# untitled.net
KiCad netlist of a schematic drawn in EAGLE
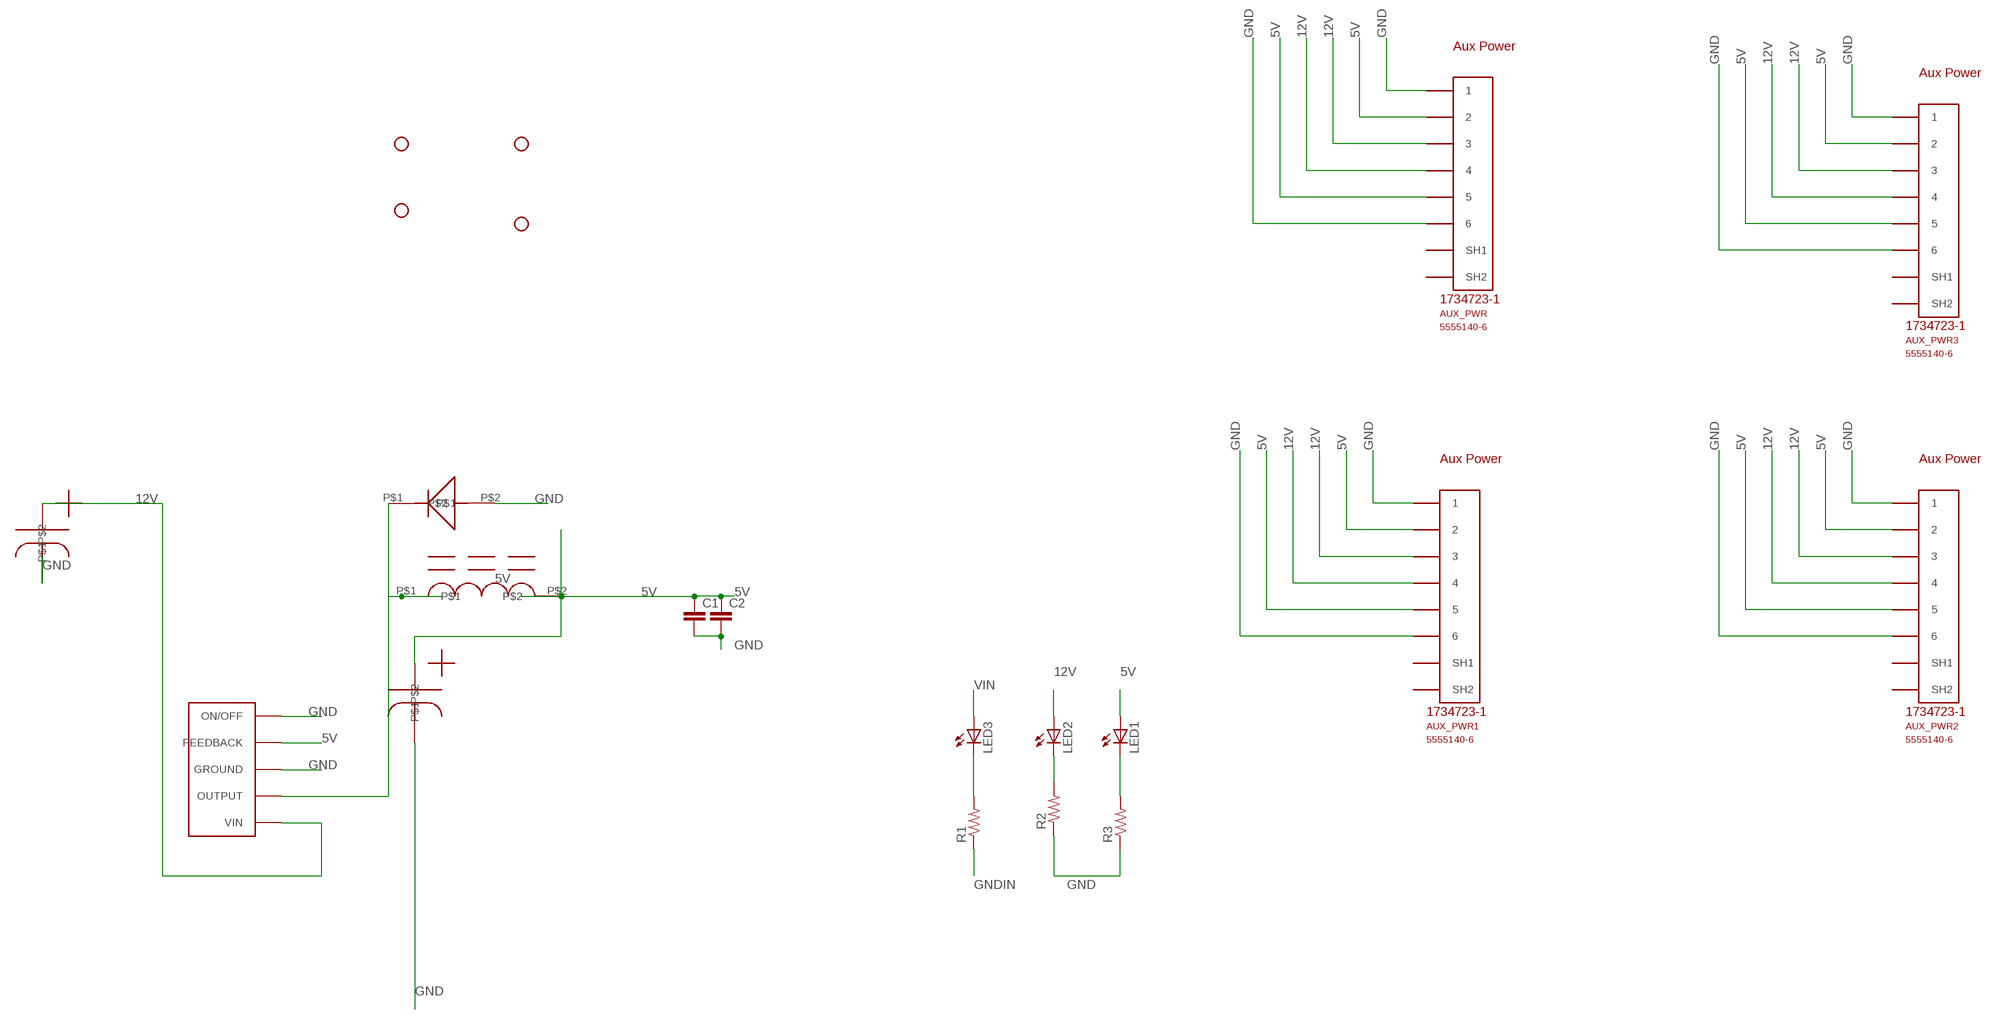
[diagram p0: schematic, sheet 1]
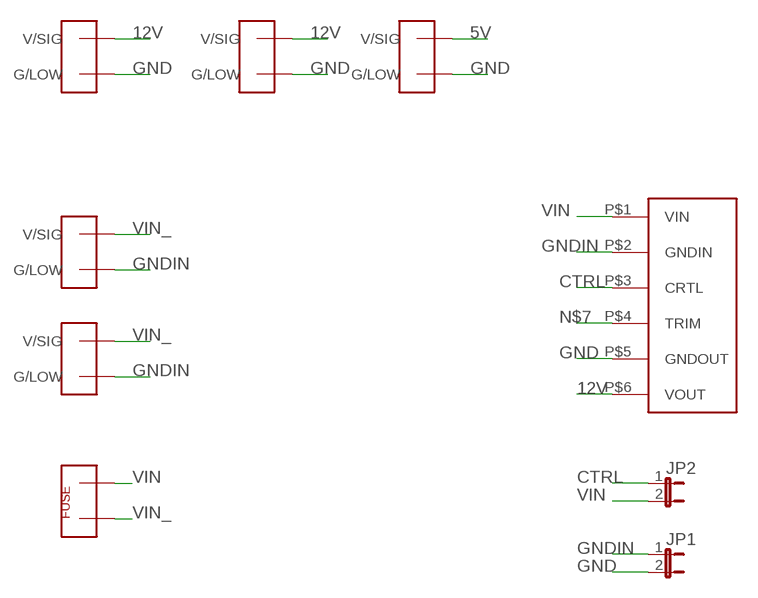
[diagram p1: schematic, sheet 2]

(export (version "E")
  (design (tool "Eeschema 10.0.6"))
  (components
    (comp (ref "AUX_PWR")
      (value "5555140-6")
      (footprint "eagle-import:1734723-1_RJ11")
      (libsource (lib "eagle-import") (part "5555140-6"))
    )
    (comp (ref "AUX_PWR1")
      (value "5555140-6")
      (footprint "eagle-import:1734723-1_RJ11")
      (libsource (lib "eagle-import") (part "5555140-6"))
    )
    (comp (ref "AUX_PWR2")
      (value "5555140-6")
      (footprint "eagle-import:1734723-1_RJ11")
      (libsource (lib "eagle-import") (part "5555140-6"))
    )
    (comp (ref "AUX_PWR3")
      (value "5555140-6")
      (footprint "eagle-import:1734723-1_RJ11")
      (libsource (lib "eagle-import") (part "5555140-6"))
    )
    (comp (ref "C1")
      (value "CAP0805")
      (footprint "eagle-import:0805")
      (libsource (lib "eagle-import") (part "CAP0805"))
    )
    (comp (ref "C2")
      (value "CAP0805")
      (footprint "eagle-import:0805")
      (libsource (lib "eagle-import") (part "CAP0805"))
    )
    (comp (ref "H1")
      (value "STAND-OFF")
      (footprint "eagle-import:STAND-OFF")
      (libsource (lib "eagle-import") (part "STAND-OFF"))
    )
    (comp (ref "H2")
      (value "STAND-OFF")
      (footprint "eagle-import:STAND-OFF")
      (libsource (lib "eagle-import") (part "STAND-OFF"))
    )
    (comp (ref "H3")
      (value "STAND-OFF")
      (footprint "eagle-import:STAND-OFF")
      (libsource (lib "eagle-import") (part "STAND-OFF"))
    )
    (comp (ref "H4")
      (value "STAND-OFF")
      (footprint "eagle-import:STAND-OFF")
      (libsource (lib "eagle-import") (part "STAND-OFF"))
    )
    (comp (ref "LED1")
      (value "LEDCHIP-LED0805")
      (footprint "eagle-import:CHIP-LED0805")
      (libsource (lib "eagle-import") (part "LEDCHIP-LED0805"))
    )
    (comp (ref "LED2")
      (value "LEDCHIP-LED0805")
      (footprint "eagle-import:CHIP-LED0805")
      (libsource (lib "eagle-import") (part "LEDCHIP-LED0805"))
    )
    (comp (ref "LED3")
      (value "LEDCHIP-LED0805")
      (footprint "eagle-import:CHIP-LED0805")
      (libsource (lib "eagle-import") (part "LEDCHIP-LED0805"))
    )
    (comp (ref "R1")
      (value "R-US_M0805")
      (footprint "eagle-import:M0805")
      (libsource (lib "eagle-import") (part "R-US_M0805"))
    )
    (comp (ref "R2")
      (value "R-US_M0805")
      (footprint "eagle-import:M0805")
      (libsource (lib "eagle-import") (part "R-US_M0805"))
    )
    (comp (ref "R3")
      (value "R-US_M0805")
      (footprint "eagle-import:M0805")
      (libsource (lib "eagle-import") (part "R-US_M0805"))
    )
    (comp (ref "U$4")
      (value "MBR360GOS")
      (footprint "eagle-import:MBR360GOS")
      (libsource (lib "eagle-import") (part "MBR360GOS"))
    )
    (comp (ref "U$7")
      (value "LM2576")
      (footprint "eagle-import:D2PAK-5")
      (libsource (lib "eagle-import") (part "LM2576"))
    )
    (comp (ref "U$8")
      (value "CAPESK107M025AC3AA")
      (footprint "eagle-import:ESK107M025AC3AA")
      (libsource (lib "eagle-import") (part "CAPESK107M025AC3AA"))
    )
    (comp (ref "U$9")
      (value "CAPESK108M025AH4EA")
      (footprint "eagle-import:ESK108M025AH4EA")
      (libsource (lib "eagle-import") (part "CAPESK108M025AH4EA"))
    )
    (comp (ref "U$10")
      (value "M1418-ND")
      (footprint "eagle-import:M1418-ND")
      (libsource (lib "eagle-import") (part "M1418-ND"))
    )
    (comp (ref "JP1")
      (value "JP1E")
      (footprint "eagle-import:JP1")
      (libsource (lib "eagle-import") (part "JP1E"))
    )
    (comp (ref "JP2")
      (value "JP1E")
      (footprint "eagle-import:JP1")
      (libsource (lib "eagle-import") (part "JP1E"))
    )
    (comp (ref "U$1")
      (value "TE770966")
      (footprint "eagle-import:2X1-MATE-N-LOCK")
      (libsource (lib "eagle-import") (part "TE770966"))
    )
    (comp (ref "U$2")
      (value "TE770966")
      (footprint "eagle-import:2X1-MATE-N-LOCK")
      (libsource (lib "eagle-import") (part "TE770966"))
    )
    (comp (ref "U$3")
      (value "TE770966")
      (footprint "eagle-import:2X1-MATE-N-LOCK")
      (libsource (lib "eagle-import") (part "TE770966"))
    )
    (comp (ref "U$12")
      (value "RPA60-2412SFW_P")
      (footprint "eagle-import:RPA60-2412SFW_P")
      (libsource (lib "eagle-import") (part "RPA60-2412SFW_P"))
    )
    (comp (ref "U$13")
      (value "FUSEMINI-BLADE")
      (footprint "eagle-import:MINI-BLADE-FUSE")
      (libsource (lib "eagle-import") (part "FUSEMINI-BLADE"))
    )
    (comp (ref "U$14")
      (value "TE770966")
      (footprint "eagle-import:2X1-MATE-N-LOCK")
      (libsource (lib "eagle-import") (part "TE770966"))
    )
    (comp (ref "U$15")
      (value "TE770966")
      (footprint "eagle-import:2X1-MATE-N-LOCK")
      (libsource (lib "eagle-import") (part "TE770966"))
    )
  )
  (nets
    (net (code "1") (name "5V") (class "Default")
      (node (ref "AUX_PWR") (pin "2") (pinfunction "2_2") (pintype "bidirectional"))
      (node (ref "AUX_PWR") (pin "5") (pinfunction "5_5") (pintype "bidirectional"))
      (node (ref "AUX_PWR1") (pin "2") (pinfunction "2_2") (pintype "bidirectional"))
      (node (ref "AUX_PWR1") (pin "5") (pinfunction "5_5") (pintype "bidirectional"))
      (node (ref "AUX_PWR2") (pin "2") (pinfunction "2_2") (pintype "bidirectional"))
      (node (ref "AUX_PWR2") (pin "5") (pinfunction "5_5") (pintype "bidirectional"))
      (node (ref "AUX_PWR3") (pin "2") (pinfunction "2_2") (pintype "bidirectional"))
      (node (ref "AUX_PWR3") (pin "5") (pinfunction "5_5") (pintype "bidirectional"))
      (node (ref "C1") (pin "1") (pinfunction "1_1") (pintype "passive"))
      (node (ref "C2") (pin "1") (pinfunction "1_1") (pintype "passive"))
      (node (ref "LED1") (pin "A") (pinfunction "A_A") (pintype "passive"))
      (node (ref "U$10") (pin "P$2") (pinfunction "P$2_P$2") (pintype "bidirectional"))
      (node (ref "U$3") (pin "CIRCUIT1") (pinfunction "V/SIG_CIRCUIT1") (pintype "bidirectional"))
      (node (ref "U$7") (pin "4") (pinfunction "FEEDBACK_4") (pintype "bidirectional"))
      (node (ref "U$9") (pin "P$1") (pinfunction "P$1_P$1") (pintype "bidirectional"))
    )
    (net (code "2") (name "12V") (class "Default")
      (node (ref "AUX_PWR") (pin "3") (pinfunction "3_3") (pintype "bidirectional"))
      (node (ref "AUX_PWR") (pin "4") (pinfunction "4_4") (pintype "bidirectional"))
      (node (ref "AUX_PWR1") (pin "3") (pinfunction "3_3") (pintype "bidirectional"))
      (node (ref "AUX_PWR1") (pin "4") (pinfunction "4_4") (pintype "bidirectional"))
      (node (ref "AUX_PWR2") (pin "3") (pinfunction "3_3") (pintype "bidirectional"))
      (node (ref "AUX_PWR2") (pin "4") (pinfunction "4_4") (pintype "bidirectional"))
      (node (ref "AUX_PWR3") (pin "3") (pinfunction "3_3") (pintype "bidirectional"))
      (node (ref "AUX_PWR3") (pin "4") (pinfunction "4_4") (pintype "bidirectional"))
      (node (ref "LED2") (pin "A") (pinfunction "A_A") (pintype "passive"))
      (node (ref "U$1") (pin "CIRCUIT1") (pinfunction "V/SIG_CIRCUIT1") (pintype "bidirectional"))
      (node (ref "U$12") (pin "P$6") (pinfunction "VOUT_P$6") (pintype "bidirectional"))
      (node (ref "U$2") (pin "CIRCUIT1") (pinfunction "V/SIG_CIRCUIT1") (pintype "bidirectional"))
      (node (ref "U$7") (pin "1") (pinfunction "VIN_1") (pintype "bidirectional"))
      (node (ref "U$8") (pin "P$1") (pinfunction "P$1_P$1") (pintype "bidirectional"))
    )
    (net (code "3") (name "CTRL") (class "Default")
      (node (ref "JP2") (pin "1") (pinfunction "1_1") (pintype "passive"))
      (node (ref "U$12") (pin "P$3") (pinfunction "CRTL_P$3") (pintype "bidirectional"))
    )
    (net (code "4") (name "GND") (class "Default")
      (node (ref "AUX_PWR") (pin "1") (pinfunction "1_1") (pintype "bidirectional"))
      (node (ref "AUX_PWR") (pin "6") (pinfunction "6_6") (pintype "bidirectional"))
      (node (ref "AUX_PWR1") (pin "1") (pinfunction "1_1") (pintype "bidirectional"))
      (node (ref "AUX_PWR1") (pin "6") (pinfunction "6_6") (pintype "bidirectional"))
      (node (ref "AUX_PWR2") (pin "1") (pinfunction "1_1") (pintype "bidirectional"))
      (node (ref "AUX_PWR2") (pin "6") (pinfunction "6_6") (pintype "bidirectional"))
      (node (ref "AUX_PWR3") (pin "1") (pinfunction "1_1") (pintype "bidirectional"))
      (node (ref "AUX_PWR3") (pin "6") (pinfunction "6_6") (pintype "bidirectional"))
      (node (ref "C1") (pin "2") (pinfunction "2_2") (pintype "passive"))
      (node (ref "C2") (pin "2") (pinfunction "2_2") (pintype "passive"))
      (node (ref "JP1") (pin "2") (pinfunction "2_2") (pintype "passive"))
      (node (ref "R2") (pin "1") (pinfunction "1_1") (pintype "passive"))
      (node (ref "R3") (pin "1") (pinfunction "1_1") (pintype "passive"))
      (node (ref "U$1") (pin "CIRCUIT2") (pinfunction "G/LOW_CIRCUIT2") (pintype "bidirectional"))
      (node (ref "U$12") (pin "P$5") (pinfunction "GNDOUT_P$5") (pintype "bidirectional"))
      (node (ref "U$2") (pin "CIRCUIT2") (pinfunction "G/LOW_CIRCUIT2") (pintype "bidirectional"))
      (node (ref "U$3") (pin "CIRCUIT2") (pinfunction "G/LOW_CIRCUIT2") (pintype "bidirectional"))
      (node (ref "U$4") (pin "P$2") (pinfunction "P$1_P$2") (pintype "bidirectional"))
      (node (ref "U$7") (pin "3") (pinfunction "GROUND_3") (pintype "bidirectional"))
      (node (ref "U$7") (pin "5") (pinfunction "ON/OFF_5") (pintype "bidirectional"))
      (node (ref "U$7") (pin "GROUND") (pinfunction "GROUND_GROUND") (pintype "bidirectional"))
      (node (ref "U$8") (pin "P$2") (pinfunction "P$2_P$2") (pintype "bidirectional"))
      (node (ref "U$9") (pin "P$2") (pinfunction "P$2_P$2") (pintype "bidirectional"))
    )
    (net (code "5") (name "GNDIN") (class "Default")
      (node (ref "JP1") (pin "1") (pinfunction "1_1") (pintype "passive"))
      (node (ref "R1") (pin "1") (pinfunction "1_1") (pintype "passive"))
      (node (ref "U$12") (pin "P$2") (pinfunction "GNDIN_P$2") (pintype "bidirectional"))
      (node (ref "U$14") (pin "CIRCUIT2") (pinfunction "G/LOW_CIRCUIT2") (pintype "bidirectional"))
      (node (ref "U$15") (pin "CIRCUIT2") (pinfunction "G/LOW_CIRCUIT2") (pintype "bidirectional"))
    )
    (net (code "6") (name "N$7") (class "Default")
      (node (ref "U$12") (pin "P$4") (pinfunction "TRIM_P$4") (pintype "bidirectional"))
    )
    (net (code "7") (name "Net-(LED1-PadC)") (class "Default")
      (node (ref "LED1") (pin "C") (pinfunction "C_C") (pintype "passive"))
      (node (ref "R3") (pin "2") (pinfunction "2_2") (pintype "passive"))
    )
    (net (code "8") (name "Net-(LED2-PadC)") (class "Default")
      (node (ref "LED2") (pin "C") (pinfunction "C_C") (pintype "passive"))
      (node (ref "R2") (pin "2") (pinfunction "2_2") (pintype "passive"))
    )
    (net (code "9") (name "Net-(LED3-PadC)") (class "Default")
      (node (ref "LED3") (pin "C") (pinfunction "C_C") (pintype "passive"))
      (node (ref "R1") (pin "2") (pinfunction "2_2") (pintype "passive"))
    )
    (net (code "10") (name "Net-(U$4-P$2)") (class "Default")
      (node (ref "U$10") (pin "P$1") (pinfunction "P$1_P$1") (pintype "bidirectional"))
      (node (ref "U$4") (pin "P$1") (pinfunction "P$2_P$1") (pintype "bidirectional"))
      (node (ref "U$7") (pin "2") (pinfunction "OUTPUT_2") (pintype "bidirectional"))
    )
    (net (code "11") (name "VIN") (class "Default")
      (node (ref "JP2") (pin "2") (pinfunction "2_2") (pintype "passive"))
      (node (ref "LED3") (pin "A") (pinfunction "A_A") (pintype "passive"))
      (node (ref "U$12") (pin "P$1") (pinfunction "VIN_P$1") (pintype "bidirectional"))
      (node (ref "U$13") (pin "OUT") (pinfunction "OUT_OUT") (pintype "bidirectional"))
    )
    (net (code "12") (name "VIN_") (class "Default")
      (node (ref "U$13") (pin "IN") (pinfunction "IN_IN") (pintype "bidirectional"))
      (node (ref "U$14") (pin "CIRCUIT1") (pinfunction "V/SIG_CIRCUIT1") (pintype "bidirectional"))
      (node (ref "U$15") (pin "CIRCUIT1") (pinfunction "V/SIG_CIRCUIT1") (pintype "bidirectional"))
    )
    (net (code "13") (name "unconnected-(AUX_PWR-PadSH1)") (class "Default")
      (node (ref "AUX_PWR") (pin "SH1") (pinfunction "SH1_SH1") (pintype "bidirectional"))
    )
    (net (code "14") (name "unconnected-(AUX_PWR-PadSH2)") (class "Default")
      (node (ref "AUX_PWR") (pin "SH2") (pinfunction "SH2_SH2") (pintype "bidirectional"))
    )
    (net (code "15") (name "unconnected-(AUX_PWR1-PadSH1)") (class "Default")
      (node (ref "AUX_PWR1") (pin "SH1") (pinfunction "SH1_SH1") (pintype "bidirectional"))
    )
    (net (code "16") (name "unconnected-(AUX_PWR1-PadSH2)") (class "Default")
      (node (ref "AUX_PWR1") (pin "SH2") (pinfunction "SH2_SH2") (pintype "bidirectional"))
    )
    (net (code "17") (name "unconnected-(AUX_PWR2-PadSH1)") (class "Default")
      (node (ref "AUX_PWR2") (pin "SH1") (pinfunction "SH1_SH1") (pintype "bidirectional"))
    )
    (net (code "18") (name "unconnected-(AUX_PWR2-PadSH2)") (class "Default")
      (node (ref "AUX_PWR2") (pin "SH2") (pinfunction "SH2_SH2") (pintype "bidirectional"))
    )
    (net (code "19") (name "unconnected-(AUX_PWR3-PadSH1)") (class "Default")
      (node (ref "AUX_PWR3") (pin "SH1") (pinfunction "SH1_SH1") (pintype "bidirectional"))
    )
    (net (code "20") (name "unconnected-(AUX_PWR3-PadSH2)") (class "Default")
      (node (ref "AUX_PWR3") (pin "SH2") (pinfunction "SH2_SH2") (pintype "bidirectional"))
    )
  )
)
